# Left_Channel_Audio.net
KiCad netlist of a schematic drawn in Altium Designer
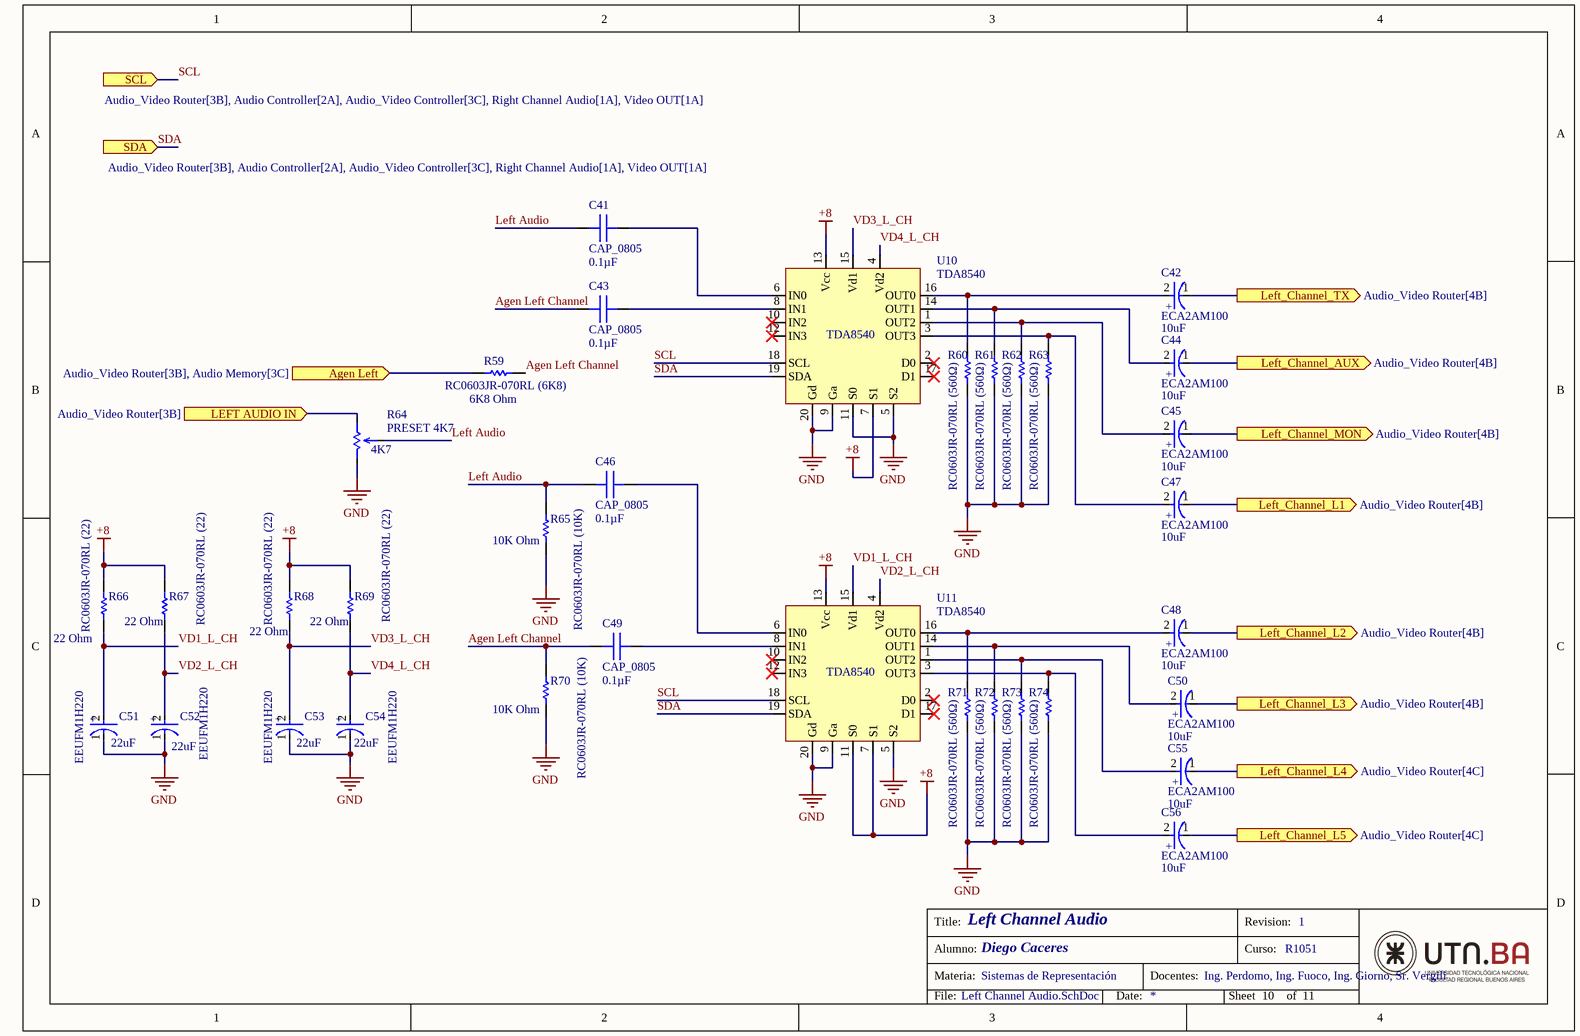
[diagram p0: Left Channel Audio.SchDoc]

(export (version "E")
  (design (tool "Eeschema 10.0.6"))
  (components
    (comp (ref "C41")
      (value "CAP_0805")
      (footprint "0805_CAPACITOR_DCACERES")
      (description "Capacitor SMD, encapsulado 0805")
      (fields (field (name "ALTIUM_VALUE") "0.1µF"))
      (libsource (lib "PF_Schlib") (part "CAPACITOR_0805_Caceres"))
    )
    (comp (ref "C42")
      (value "ECA2AM100")
      (footprint "FP-RAD-TH-D_5_0_5-L_11_1-MFG")
      (description "Aluminum Electrolytic Capacitors (Radial Lead Type) 10uF ±20% 100V")
      (fields
        (field (name "CAPACITANCE") "10uF")
        (field (name "VOLTAGE") "100V")
        (field (name "TOLERANCE") "20%")
      )
      (libsource (lib "Altium Content Vault") (part "a00bbbee19879c290e62620ae7e47b1"))
    )
    (comp (ref "C43")
      (value "CAP_0805")
      (footprint "0805_CAPACITOR_DCACERES")
      (description "Capacitor SMD, encapsulado 0805")
      (fields (field (name "ALTIUM_VALUE") "0.1µF"))
      (libsource (lib "PF_Schlib") (part "CAPACITOR_0805_Caceres"))
    )
    (comp (ref "C44")
      (value "ECA2AM100")
      (footprint "FP-RAD-TH-D_5_0_5-L_11_1-MFG")
      (description "Aluminum Electrolytic Capacitors (Radial Lead Type) 10uF ±20% 100V")
      (fields
        (field (name "CAPACITANCE") "10uF")
        (field (name "VOLTAGE") "100V")
        (field (name "TOLERANCE") "20%")
      )
      (libsource (lib "Altium Content Vault") (part "a00bbbee19879c290e62620ae7e47b1"))
    )
    (comp (ref "C45")
      (value "ECA2AM100")
      (footprint "FP-RAD-TH-D_5_0_5-L_11_1-MFG")
      (description "Aluminum Electrolytic Capacitors (Radial Lead Type) 10uF ±20% 100V")
      (fields
        (field (name "CAPACITANCE") "10uF")
        (field (name "VOLTAGE") "100V")
        (field (name "TOLERANCE") "20%")
      )
      (libsource (lib "Altium Content Vault") (part "a00bbbee19879c290e62620ae7e47b1"))
    )
    (comp (ref "C46")
      (value "CAP_0805")
      (footprint "0805_CAPACITOR_DCACERES")
      (description "Capacitor SMD, encapsulado 0805")
      (fields (field (name "ALTIUM_VALUE") "0.1µF"))
      (libsource (lib "PF_Schlib") (part "CAPACITOR_0805_Caceres"))
    )
    (comp (ref "C47")
      (value "ECA2AM100")
      (footprint "FP-RAD-TH-D_5_0_5-L_11_1-MFG")
      (description "Aluminum Electrolytic Capacitors (Radial Lead Type) 10uF ±20% 100V")
      (fields
        (field (name "CAPACITANCE") "10uF")
        (field (name "VOLTAGE") "100V")
        (field (name "TOLERANCE") "20%")
      )
      (libsource (lib "Altium Content Vault") (part "a00bbbee19879c290e62620ae7e47b1"))
    )
    (comp (ref "C48")
      (value "ECA2AM100")
      (footprint "FP-RAD-TH-D_5_0_5-L_11_1-MFG")
      (description "Aluminum Electrolytic Capacitors (Radial Lead Type) 10uF ±20% 100V")
      (fields
        (field (name "CAPACITANCE") "10uF")
        (field (name "VOLTAGE") "100V")
        (field (name "TOLERANCE") "20%")
      )
      (libsource (lib "Altium Content Vault") (part "a00bbbee19879c290e62620ae7e47b1"))
    )
    (comp (ref "C49")
      (value "CAP_0805")
      (footprint "0805_CAPACITOR_DCACERES")
      (description "Capacitor SMD, encapsulado 0805")
      (fields (field (name "ALTIUM_VALUE") "0.1µF"))
      (libsource (lib "PF_Schlib") (part "CAPACITOR_0805_Caceres"))
    )
    (comp (ref "C50")
      (value "ECA2AM100")
      (footprint "FP-RAD-TH-D_5_0_5-L_11_1-MFG")
      (description "Aluminum Electrolytic Capacitors (Radial Lead Type) 10uF ±20% 100V")
      (fields
        (field (name "CAPACITANCE") "10uF")
        (field (name "VOLTAGE") "100V")
        (field (name "TOLERANCE") "20%")
      )
      (libsource (lib "Altium Content Vault") (part "a00bbbee19879c290e62620ae7e47b1"))
    )
    (comp (ref "C51")
      (value "EEUFM1H220")
      (footprint "FP-RAD-TH-D_5_0_5-L_11_1-MFG")
      (description "Aluminum Electrolytic Capacitors (Radial Lead Type) 22uF ±20% 50V")
      (fields
        (field (name "TOLERANCE") "20%")
        (field (name "VOLTAGE") "50V")
        (field (name "CAPACITANCE") "22uF")
      )
      (libsource (lib "Altium Content Vault") (part "a00bbbee19879c290e62620ae7e47b1"))
    )
    (comp (ref "C52")
      (value "EEUFM1H220")
      (footprint "FP-RAD-TH-D_5_0_5-L_11_1-MFG")
      (description "Aluminum Electrolytic Capacitors (Radial Lead Type) 22uF ±20% 50V")
      (fields
        (field (name "TOLERANCE") "20%")
        (field (name "VOLTAGE") "50V")
        (field (name "CAPACITANCE") "22uF")
      )
      (libsource (lib "Altium Content Vault") (part "a00bbbee19879c290e62620ae7e47b1"))
    )
    (comp (ref "C53")
      (value "EEUFM1H220")
      (footprint "FP-RAD-TH-D_5_0_5-L_11_1-MFG")
      (description "Aluminum Electrolytic Capacitors (Radial Lead Type) 22uF ±20% 50V")
      (fields
        (field (name "TOLERANCE") "20%")
        (field (name "VOLTAGE") "50V")
        (field (name "CAPACITANCE") "22uF")
      )
      (libsource (lib "Altium Content Vault") (part "a00bbbee19879c290e62620ae7e47b1"))
    )
    (comp (ref "C54")
      (value "EEUFM1H220")
      (footprint "FP-RAD-TH-D_5_0_5-L_11_1-MFG")
      (description "Aluminum Electrolytic Capacitors (Radial Lead Type) 22uF ±20% 50V")
      (fields
        (field (name "TOLERANCE") "20%")
        (field (name "VOLTAGE") "50V")
        (field (name "CAPACITANCE") "22uF")
      )
      (libsource (lib "Altium Content Vault") (part "a00bbbee19879c290e62620ae7e47b1"))
    )
    (comp (ref "C55")
      (value "ECA2AM100")
      (footprint "FP-RAD-TH-D_5_0_5-L_11_1-MFG")
      (description "Aluminum Electrolytic Capacitors (Radial Lead Type) 10uF ±20% 100V")
      (fields
        (field (name "CAPACITANCE") "10uF")
        (field (name "VOLTAGE") "100V")
        (field (name "TOLERANCE") "20%")
      )
      (libsource (lib "Altium Content Vault") (part "a00bbbee19879c290e62620ae7e47b1"))
    )
    (comp (ref "C56")
      (value "ECA2AM100")
      (footprint "FP-RAD-TH-D_5_0_5-L_11_1-MFG")
      (description "Aluminum Electrolytic Capacitors (Radial Lead Type) 10uF ±20% 100V")
      (fields
        (field (name "CAPACITANCE") "10uF")
        (field (name "VOLTAGE") "100V")
        (field (name "TOLERANCE") "20%")
      )
      (libsource (lib "Altium Content Vault") (part "a00bbbee19879c290e62620ae7e47b1"))
    )
    (comp (ref "R59")
      (value "RC0603JR-070RL (6K8)")
      (footprint "RESC1608X55X25ML10T15")
      (description "Chip Resistor, 0 Ohm, +/- 5%, 0.1 W, -55 to 155 degC, 0603 (1608 Metric), RoHS, Tape and Reel")
      (fields
        (field (name "TOLERANCE") "5%")
        (field (name "RESISTANCE") "6K8 Ohm")
        (field (name "MANUFACTURER") "Yageo")
      )
      (libsource (lib "Altium Content Vault") (part "RES-2"))
    )
    (comp (ref "R60")
      (value "RC0603JR-070RL (560Ω)")
      (footprint "RESC1608X55X25ML10T15")
      (description "Chip Resistor, 0 Ohm, +/- 5%, 0.1 W, -55 to 155 degC, 0603 (1608 Metric), RoHS, Tape and Reel")
      (fields (field (name "TOLERANCE") "5%") (field (name "MANUFACTURER") "Yageo"))
      (libsource (lib "Altium Content Vault") (part "RES-2"))
    )
    (comp (ref "R61")
      (value "RC0603JR-070RL (560Ω)")
      (footprint "RESC1608X55X25ML10T15")
      (description "Chip Resistor, 0 Ohm, +/- 5%, 0.1 W, -55 to 155 degC, 0603 (1608 Metric), RoHS, Tape and Reel")
      (fields (field (name "TOLERANCE") "5%") (field (name "MANUFACTURER") "Yageo"))
      (libsource (lib "Altium Content Vault") (part "RES-2"))
    )
    (comp (ref "R62")
      (value "RC0603JR-070RL (560Ω)")
      (footprint "RESC1608X55X25ML10T15")
      (description "Chip Resistor, 0 Ohm, +/- 5%, 0.1 W, -55 to 155 degC, 0603 (1608 Metric), RoHS, Tape and Reel")
      (fields (field (name "TOLERANCE") "5%") (field (name "MANUFACTURER") "Yageo"))
      (libsource (lib "Altium Content Vault") (part "RES-2"))
    )
    (comp (ref "R63")
      (value "RC0603JR-070RL (560Ω)")
      (footprint "RESC1608X55X25ML10T15")
      (description "Chip Resistor, 0 Ohm, +/- 5%, 0.1 W, -55 to 155 degC, 0603 (1608 Metric), RoHS, Tape and Reel")
      (fields (field (name "TOLERANCE") "5%") (field (name "MANUFACTURER") "Yageo"))
      (libsource (lib "Altium Content Vault") (part "RES-2"))
    )
    (comp (ref "R64")
      (value "PRESET 4K7")
      (footprint "3386P_PRESET_4K7_DCaceres")
      (description "Preset 4K7, Thru HoleManufacturer Part Search 3386P-1-472LF")
      (fields (field (name "ALTIUM_VALUE") "4K7") (field (name "PARTNUMBER") "3386P-1-472LF"))
      (libsource (lib "PF_Schlib") (part "Preset_4K7_Caceres"))
    )
    (comp (ref "R65")
      (value "RC0603JR-070RL (10K)")
      (footprint "RESC1608X55X25ML10T15")
      (description "Chip Resistor, 0 Ohm, +/- 5%, 0.1 W, -55 to 155 degC, 0603 (1608 Metric), RoHS, Tape and Reel")
      (fields
        (field (name "TOLERANCE") "5%")
        (field (name "RESISTANCE") "10K Ohm")
        (field (name "MANUFACTURER") "Yageo")
      )
      (libsource (lib "Altium Content Vault") (part "RES-2"))
    )
    (comp (ref "R66")
      (value "RC0603JR-070RL (22)")
      (footprint "RESC1608X55X25ML10T15")
      (description "Chip Resistor, 0 Ohm, +/- 5%, 0.1 W, -55 to 155 degC, 0603 (1608 Metric), RoHS, Tape and Reel")
      (fields
        (field (name "TOLERANCE") "5%")
        (field (name "RESISTANCE") "22 Ohm")
        (field (name "MANUFACTURER") "Yageo")
      )
      (libsource (lib "Altium Content Vault") (part "RES-2"))
    )
    (comp (ref "R67")
      (value "RC0603JR-070RL (22)")
      (footprint "RESC1608X55X25ML10T15")
      (description "Chip Resistor, 0 Ohm, +/- 5%, 0.1 W, -55 to 155 degC, 0603 (1608 Metric), RoHS, Tape and Reel")
      (fields
        (field (name "TOLERANCE") "5%")
        (field (name "RESISTANCE") "22 Ohm")
        (field (name "MANUFACTURER") "Yageo")
      )
      (libsource (lib "Altium Content Vault") (part "RES-2"))
    )
    (comp (ref "R68")
      (value "RC0603JR-070RL (22)")
      (footprint "RESC1608X55X25ML10T15")
      (description "Chip Resistor, 0 Ohm, +/- 5%, 0.1 W, -55 to 155 degC, 0603 (1608 Metric), RoHS, Tape and Reel")
      (fields
        (field (name "TOLERANCE") "5%")
        (field (name "RESISTANCE") "22 Ohm")
        (field (name "MANUFACTURER") "Yageo")
      )
      (libsource (lib "Altium Content Vault") (part "RES-2"))
    )
    (comp (ref "R69")
      (value "RC0603JR-070RL (22)")
      (footprint "RESC1608X55X25ML10T15")
      (description "Chip Resistor, 0 Ohm, +/- 5%, 0.1 W, -55 to 155 degC, 0603 (1608 Metric), RoHS, Tape and Reel")
      (fields
        (field (name "TOLERANCE") "5%")
        (field (name "RESISTANCE") "22 Ohm")
        (field (name "MANUFACTURER") "Yageo")
      )
      (libsource (lib "Altium Content Vault") (part "RES-2"))
    )
    (comp (ref "R70")
      (value "RC0603JR-070RL (10K)")
      (footprint "RESC1608X55X25ML10T15")
      (description "Chip Resistor, 0 Ohm, +/- 5%, 0.1 W, -55 to 155 degC, 0603 (1608 Metric), RoHS, Tape and Reel")
      (fields
        (field (name "TOLERANCE") "5%")
        (field (name "RESISTANCE") "10K Ohm")
        (field (name "MANUFACTURER") "Yageo")
      )
      (libsource (lib "Altium Content Vault") (part "RES-2"))
    )
    (comp (ref "R71")
      (value "RC0603JR-070RL (560Ω)")
      (footprint "RESC1608X55X25ML10T15")
      (description "Chip Resistor, 0 Ohm, +/- 5%, 0.1 W, -55 to 155 degC, 0603 (1608 Metric), RoHS, Tape and Reel")
      (fields (field (name "TOLERANCE") "5%") (field (name "MANUFACTURER") "Yageo"))
      (libsource (lib "Altium Content Vault") (part "RES-2"))
    )
    (comp (ref "R72")
      (value "RC0603JR-070RL (560Ω)")
      (footprint "RESC1608X55X25ML10T15")
      (description "Chip Resistor, 0 Ohm, +/- 5%, 0.1 W, -55 to 155 degC, 0603 (1608 Metric), RoHS, Tape and Reel")
      (fields (field (name "TOLERANCE") "5%") (field (name "MANUFACTURER") "Yageo"))
      (libsource (lib "Altium Content Vault") (part "RES-2"))
    )
    (comp (ref "R73")
      (value "RC0603JR-070RL (560Ω)")
      (footprint "RESC1608X55X25ML10T15")
      (description "Chip Resistor, 0 Ohm, +/- 5%, 0.1 W, -55 to 155 degC, 0603 (1608 Metric), RoHS, Tape and Reel")
      (fields (field (name "TOLERANCE") "5%") (field (name "MANUFACTURER") "Yageo"))
      (libsource (lib "Altium Content Vault") (part "RES-2"))
    )
    (comp (ref "R74")
      (value "RC0603JR-070RL (560Ω)")
      (footprint "RESC1608X55X25ML10T15")
      (description "Chip Resistor, 0 Ohm, +/- 5%, 0.1 W, -55 to 155 degC, 0603 (1608 Metric), RoHS, Tape and Reel")
      (fields (field (name "TOLERANCE") "5%") (field (name "MANUFACTURER") "Yageo"))
      (libsource (lib "Altium Content Vault") (part "RES-2"))
    )
    (comp (ref "U10")
      (value "TDA8540")
      (footprint "SOT146-1_DIP20_TDA8540_DCACERES")
      (description "TDA8540, Thtu Hole\r\nPlastic dual in-line package; 20 leads (300 mil); DIP20; SOT146-1.")
      (libsource (lib "PF_Schlib") (part "TDA8540_Caceres"))
    )
    (comp (ref "U11")
      (value "TDA8540")
      (footprint "SOT146-1_DIP20_TDA8540_DCACERES")
      (description "TDA8540, Thtu Hole\r\nPlastic dual in-line package; 20 leads (300 mil); DIP20; SOT146-1.")
      (libsource (lib "PF_Schlib") (part "TDA8540_Caceres"))
    )
  )
  (nets
    (net (code "1") (name "+8") (class "Default")
      (node (ref "R66") (pin "2") (pinfunction "2_2") (pintype "passive"))
      (node (ref "R67") (pin "2") (pinfunction "2_2") (pintype "passive"))
      (node (ref "R68") (pin "2") (pinfunction "2_2") (pintype "passive"))
      (node (ref "R69") (pin "2") (pinfunction "2_2") (pintype "passive"))
      (node (ref "U10") (pin "13") (pinfunction "Vcc_13") (pintype "passive"))
      (node (ref "U10") (pin "7") (pinfunction "S1_7") (pintype "passive"))
      (node (ref "U11") (pin "11") (pinfunction "S0_11") (pintype "passive"))
      (node (ref "U11") (pin "13") (pinfunction "Vcc_13") (pintype "passive"))
      (node (ref "U11") (pin "7") (pinfunction "S1_7") (pintype "passive"))
    )
    (net (code "2") (name "/Agen Left") (class "Default")
      (node (ref "R59") (pin "1") (pinfunction "1_1") (pintype "passive"))
    )
    (net (code "3") (name "/Agen Left Channel") (class "Default")
      (node (ref "C43") (pin "1") (pinfunction "1_1") (pintype "passive"))
      (node (ref "C49") (pin "1") (pinfunction "1_1") (pintype "passive"))
      (node (ref "R59") (pin "2") (pinfunction "2_2") (pintype "passive"))
      (node (ref "R70") (pin "2") (pinfunction "2_2") (pintype "passive"))
    )
    (net (code "4") (name "/LEFT AUDIO IN") (class "Default")
      (node (ref "R64") (pin "2") (pinfunction "1_2") (pintype "passive"))
    )
    (net (code "5") (name "/Left Audio") (class "Default")
      (node (ref "C41") (pin "1") (pinfunction "1_1") (pintype "passive"))
      (node (ref "C46") (pin "1") (pinfunction "1_1") (pintype "passive"))
      (node (ref "R64") (pin "3") (pinfunction "3_3") (pintype "passive"))
      (node (ref "R65") (pin "2") (pinfunction "2_2") (pintype "passive"))
    )
    (net (code "6") (name "/Left_Channel_AUX") (class "Default")
      (node (ref "C44") (pin "1") (pinfunction "C_1") (pintype "passive"))
    )
    (net (code "7") (name "/Left_Channel_L1") (class "Default")
      (node (ref "C47") (pin "1") (pinfunction "C_1") (pintype "passive"))
    )
    (net (code "8") (name "/Left_Channel_L2") (class "Default")
      (node (ref "C48") (pin "1") (pinfunction "C_1") (pintype "passive"))
    )
    (net (code "9") (name "/Left_Channel_L3") (class "Default")
      (node (ref "C50") (pin "1") (pinfunction "C_1") (pintype "passive"))
    )
    (net (code "10") (name "/Left_Channel_L4") (class "Default")
      (node (ref "C55") (pin "1") (pinfunction "C_1") (pintype "passive"))
    )
    (net (code "11") (name "/Left_Channel_L5") (class "Default")
      (node (ref "C56") (pin "1") (pinfunction "C_1") (pintype "passive"))
    )
    (net (code "12") (name "/Left_Channel_MON") (class "Default")
      (node (ref "C45") (pin "1") (pinfunction "C_1") (pintype "passive"))
    )
    (net (code "13") (name "/Left_Channel_TX") (class "Default")
      (node (ref "C42") (pin "1") (pinfunction "C_1") (pintype "passive"))
    )
    (net (code "14") (name "/SCL") (class "Default")
      (node (ref "U10") (pin "18") (pinfunction "SCL_18") (pintype "passive"))
      (node (ref "U11") (pin "18") (pinfunction "SCL_18") (pintype "passive"))
    )
    (net (code "15") (name "/SDA") (class "Default")
      (node (ref "U10") (pin "19") (pinfunction "SDA_19") (pintype "passive"))
      (node (ref "U11") (pin "19") (pinfunction "SDA_19") (pintype "passive"))
    )
    (net (code "16") (name "/VD1_L_CH") (class "Default")
      (node (ref "C51") (pin "2") (pinfunction "A_2") (pintype "passive"))
      (node (ref "R66") (pin "1") (pinfunction "1_1") (pintype "passive"))
      (node (ref "U11") (pin "15") (pinfunction "Vd1_15") (pintype "passive"))
    )
    (net (code "17") (name "/VD2_L_CH") (class "Default")
      (node (ref "C52") (pin "2") (pinfunction "A_2") (pintype "passive"))
      (node (ref "R67") (pin "1") (pinfunction "1_1") (pintype "passive"))
      (node (ref "U11") (pin "4") (pinfunction "Vd2_4") (pintype "passive"))
    )
    (net (code "18") (name "/VD3_L_CH") (class "Default")
      (node (ref "C53") (pin "2") (pinfunction "A_2") (pintype "passive"))
      (node (ref "R68") (pin "1") (pinfunction "1_1") (pintype "passive"))
      (node (ref "U10") (pin "15") (pinfunction "Vd1_15") (pintype "passive"))
    )
    (net (code "19") (name "/VD4_L_CH") (class "Default")
      (node (ref "C54") (pin "2") (pinfunction "A_2") (pintype "passive"))
      (node (ref "R69") (pin "1") (pinfunction "1_1") (pintype "passive"))
      (node (ref "U10") (pin "4") (pinfunction "Vd2_4") (pintype "passive"))
    )
    (net (code "20") (name "GND") (class "Default")
      (node (ref "C51") (pin "1") (pinfunction "C_1") (pintype "passive"))
      (node (ref "C52") (pin "1") (pinfunction "C_1") (pintype "passive"))
      (node (ref "C53") (pin "1") (pinfunction "C_1") (pintype "passive"))
      (node (ref "C54") (pin "1") (pinfunction "C_1") (pintype "passive"))
      (node (ref "R60") (pin "2") (pinfunction "2_2") (pintype "passive"))
      (node (ref "R61") (pin "2") (pinfunction "2_2") (pintype "passive"))
      (node (ref "R62") (pin "2") (pinfunction "2_2") (pintype "passive"))
      (node (ref "R63") (pin "2") (pinfunction "2_2") (pintype "passive"))
      (node (ref "R64") (pin "1") (pinfunction "1_1") (pintype "passive"))
      (node (ref "R65") (pin "1") (pinfunction "1_1") (pintype "passive"))
      (node (ref "R70") (pin "1") (pinfunction "1_1") (pintype "passive"))
      (node (ref "R71") (pin "2") (pinfunction "2_2") (pintype "passive"))
      (node (ref "R72") (pin "2") (pinfunction "2_2") (pintype "passive"))
      (node (ref "R73") (pin "2") (pinfunction "2_2") (pintype "passive"))
      (node (ref "R74") (pin "2") (pinfunction "2_2") (pintype "passive"))
      (node (ref "U10") (pin "11") (pinfunction "S0_11") (pintype "passive"))
      (node (ref "U10") (pin "20") (pinfunction "Gd_20") (pintype "passive"))
      (node (ref "U10") (pin "5") (pinfunction "S2_5") (pintype "passive"))
      (node (ref "U10") (pin "9") (pinfunction "Ga_9") (pintype "passive"))
      (node (ref "U11") (pin "20") (pinfunction "Gd_20") (pintype "passive"))
      (node (ref "U11") (pin "5") (pinfunction "S2_5") (pintype "passive"))
      (node (ref "U11") (pin "9") (pinfunction "Ga_9") (pintype "passive"))
    )
    (net (code "21") (name "Net-(C42-A)") (class "Default")
      (node (ref "C42") (pin "2") (pinfunction "A_2") (pintype "passive"))
      (node (ref "R60") (pin "1") (pinfunction "1_1") (pintype "passive"))
      (node (ref "U10") (pin "16") (pinfunction "OUT0_16") (pintype "passive"))
    )
    (net (code "22") (name "Net-(C44-A)") (class "Default")
      (node (ref "C44") (pin "2") (pinfunction "A_2") (pintype "passive"))
      (node (ref "R61") (pin "1") (pinfunction "1_1") (pintype "passive"))
      (node (ref "U10") (pin "14") (pinfunction "OUT1_14") (pintype "passive"))
    )
    (net (code "23") (name "Net-(C45-A)") (class "Default")
      (node (ref "C45") (pin "2") (pinfunction "A_2") (pintype "passive"))
      (node (ref "R62") (pin "1") (pinfunction "1_1") (pintype "passive"))
      (node (ref "U10") (pin "1") (pinfunction "OUT2_1") (pintype "passive"))
    )
    (net (code "24") (name "Net-(C47-A)") (class "Default")
      (node (ref "C47") (pin "2") (pinfunction "A_2") (pintype "passive"))
      (node (ref "R63") (pin "1") (pinfunction "1_1") (pintype "passive"))
      (node (ref "U10") (pin "3") (pinfunction "OUT3_3") (pintype "passive"))
    )
    (net (code "25") (name "Net-(C48-A)") (class "Default")
      (node (ref "C48") (pin "2") (pinfunction "A_2") (pintype "passive"))
      (node (ref "R71") (pin "1") (pinfunction "1_1") (pintype "passive"))
      (node (ref "U11") (pin "16") (pinfunction "OUT0_16") (pintype "passive"))
    )
    (net (code "26") (name "Net-(C50-A)") (class "Default")
      (node (ref "C50") (pin "2") (pinfunction "A_2") (pintype "passive"))
      (node (ref "R72") (pin "1") (pinfunction "1_1") (pintype "passive"))
      (node (ref "U11") (pin "14") (pinfunction "OUT1_14") (pintype "passive"))
    )
    (net (code "27") (name "Net-(C55-A)") (class "Default")
      (node (ref "C55") (pin "2") (pinfunction "A_2") (pintype "passive"))
      (node (ref "R73") (pin "1") (pinfunction "1_1") (pintype "passive"))
      (node (ref "U11") (pin "1") (pinfunction "OUT2_1") (pintype "passive"))
    )
    (net (code "28") (name "Net-(C56-A)") (class "Default")
      (node (ref "C56") (pin "2") (pinfunction "A_2") (pintype "passive"))
      (node (ref "R74") (pin "1") (pinfunction "1_1") (pintype "passive"))
      (node (ref "U11") (pin "3") (pinfunction "OUT3_3") (pintype "passive"))
    )
    (net (code "29") (name "Net-(U10-IN0)") (class "Default")
      (node (ref "C41") (pin "2") (pinfunction "2_2") (pintype "passive"))
      (node (ref "U10") (pin "6") (pinfunction "IN0_6") (pintype "passive"))
    )
    (net (code "30") (name "Net-(U10-IN1)") (class "Default")
      (node (ref "C43") (pin "2") (pinfunction "2_2") (pintype "passive"))
      (node (ref "U10") (pin "8") (pinfunction "IN1_8") (pintype "passive"))
    )
    (net (code "31") (name "Net-(U11-IN0)") (class "Default")
      (node (ref "C46") (pin "2") (pinfunction "2_2") (pintype "passive"))
      (node (ref "U11") (pin "6") (pinfunction "IN0_6") (pintype "passive"))
    )
    (net (code "32") (name "Net-(U11-IN1)") (class "Default")
      (node (ref "C49") (pin "2") (pinfunction "2_2") (pintype "passive"))
      (node (ref "U11") (pin "8") (pinfunction "IN1_8") (pintype "passive"))
    )
    (net (code "33") (name "unconnected-(U10-D0-Pad2)") (class "Default")
      (node (ref "U10") (pin "2") (pinfunction "D0_2") (pintype "passive+no_connect"))
    )
    (net (code "34") (name "unconnected-(U10-D1-Pad17)") (class "Default")
      (node (ref "U10") (pin "17") (pinfunction "D1_17") (pintype "passive+no_connect"))
    )
    (net (code "35") (name "unconnected-(U10-IN2-Pad10)") (class "Default")
      (node (ref "U10") (pin "10") (pinfunction "IN2_10") (pintype "passive+no_connect"))
    )
    (net (code "36") (name "unconnected-(U10-IN3-Pad12)") (class "Default")
      (node (ref "U10") (pin "12") (pinfunction "IN3_12") (pintype "passive+no_connect"))
    )
    (net (code "37") (name "unconnected-(U11-D0-Pad2)") (class "Default")
      (node (ref "U11") (pin "2") (pinfunction "D0_2") (pintype "passive+no_connect"))
    )
    (net (code "38") (name "unconnected-(U11-D1-Pad17)") (class "Default")
      (node (ref "U11") (pin "17") (pinfunction "D1_17") (pintype "passive+no_connect"))
    )
    (net (code "39") (name "unconnected-(U11-IN2-Pad10)") (class "Default")
      (node (ref "U11") (pin "10") (pinfunction "IN2_10") (pintype "passive+no_connect"))
    )
    (net (code "40") (name "unconnected-(U11-IN3-Pad12)") (class "Default")
      (node (ref "U11") (pin "12") (pinfunction "IN3_12") (pintype "passive+no_connect"))
    )
  )
)
